# POWER.net
KiCad netlist of a schematic drawn in Altium Designer
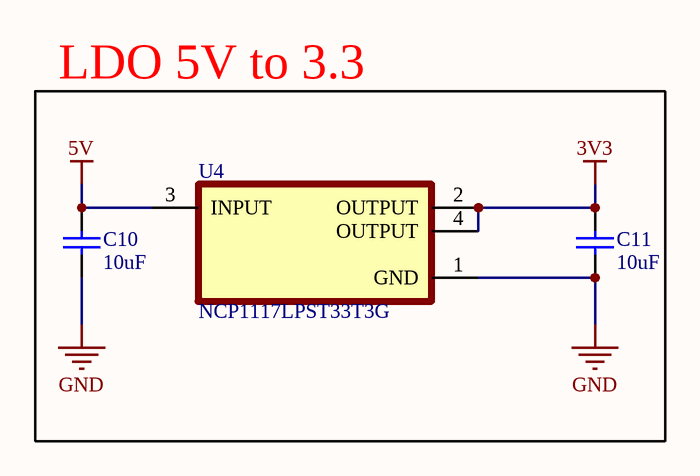
[diagram p0: POWER.SchDoc]

(export (version "E")
  (design (tool "Eeschema 10.0.6"))
  (components
    (comp (ref "C10")
      (value "10uF")
      (footprint "CAP_0402L")
      (description "CAP CER 10µF 16V X7R 10% 0402")
      (fields (field (name "TOLERANCE") "10%"))
      (libsource (lib "PCB_training_Project") (part "CAP CER 10µF"))
    )
    (comp (ref "C11")
      (value "10uF")
      (footprint "CAP_0402L")
      (description "CAP CER 10µF 16V X7R 10% 0402")
      (fields (field (name "TOLERANCE") "10%"))
      (libsource (lib "PCB_training_Project") (part "CAP CER 10µF"))
    )
    (comp (ref "U4")
      (value "NCP1117LPST33T3G")
      (footprint "SOT230P700X175-4N")
      (description "Linear Voltage Regulator IC Positive Fixed 1 Output 1A SOT-223")
      (fields (field (name "MF") "ON Semiconductor"))
      (libsource (lib "PCB_training_Project") (part "NCP1117LPST33T3G"))
    )
  )
  (nets
    (net (code "1") (name "3V3") (class "Default")
      (node (ref "C11") (pin "2") (pinfunction "2_2") (pintype "passive"))
      (node (ref "U4") (pin "2") (pinfunction "OUTPUT_2") (pintype "passive"))
      (node (ref "U4") (pin "4") (pinfunction "OUTPUT_4") (pintype "passive"))
    )
    (net (code "2") (name "5V") (class "Default")
      (node (ref "C10") (pin "2") (pinfunction "2_2") (pintype "passive"))
      (node (ref "U4") (pin "3") (pinfunction "INPUT_3") (pintype "passive"))
    )
    (net (code "3") (name "GND") (class "Default")
      (node (ref "C10") (pin "1") (pinfunction "1_1") (pintype "passive"))
      (node (ref "C11") (pin "1") (pinfunction "1_1") (pintype "passive"))
      (node (ref "U4") (pin "1") (pinfunction "GND_1") (pintype "power_in"))
    )
  )
)
